# analog_filterung.net
KiCad netlist of a schematic drawn in Altium Designer
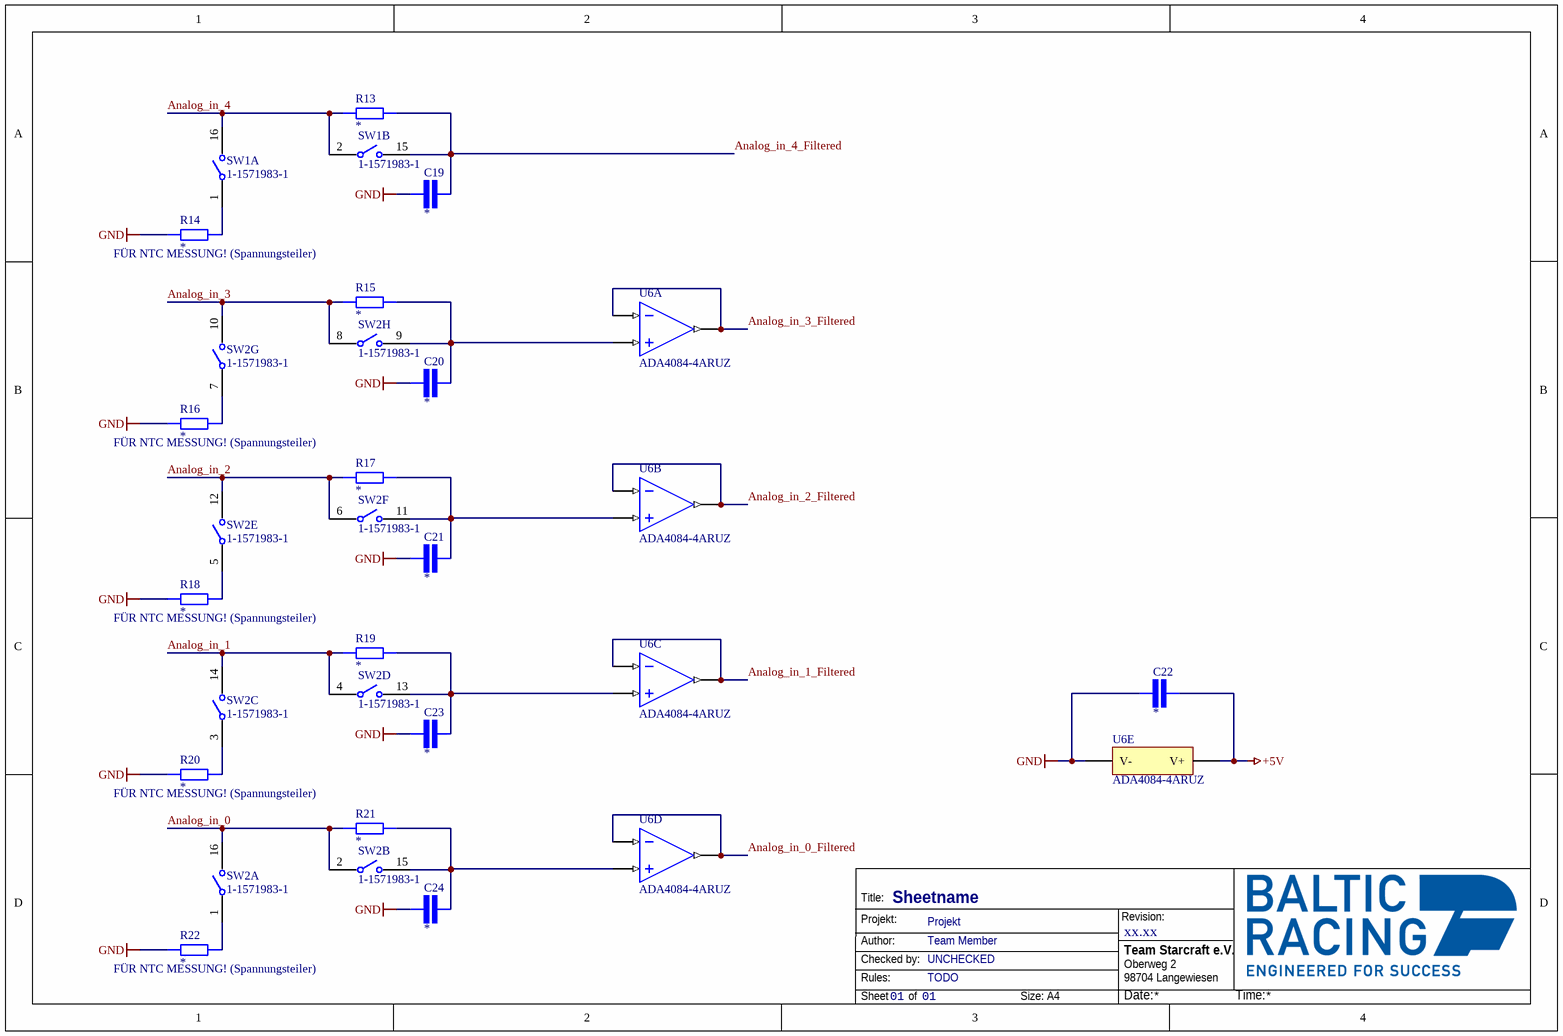
[diagram p0: analog filterung.SchDoc]

(export (version "E")
  (design (tool "Eeschema 10.0.6"))
  (components
    (comp (ref "C19")
      (value "SMD Capacitor")
      (footprint "CAP 0603/1608")
      (description "Capacitor with multiple Footprints")
      (fields (field (name "ALTIUM_VALUE") "*"))
      (libsource (lib "") (part "SMD Capacitor_1"))
    )
    (comp (ref "C20")
      (value "SMD Capacitor")
      (footprint "CAP 0603/1608")
      (description "Capacitor with multiple Footprints")
      (fields (field (name "ALTIUM_VALUE") "*"))
      (libsource (lib "") (part "SMD Capacitor_1"))
    )
    (comp (ref "C21")
      (value "SMD Capacitor")
      (footprint "CAP 0603/1608")
      (description "Capacitor with multiple Footprints")
      (fields (field (name "ALTIUM_VALUE") "*"))
      (libsource (lib "") (part "SMD Capacitor_1"))
    )
    (comp (ref "C22")
      (value "SMD Capacitor")
      (footprint "CAP 0603/1608")
      (description "Capacitor with multiple Footprints")
      (fields (field (name "ALTIUM_VALUE") "*"))
      (libsource (lib "Standardbauteile") (part "SMD Capacitor"))
    )
    (comp (ref "C23")
      (value "SMD Capacitor")
      (footprint "CAP 0603/1608")
      (description "Capacitor with multiple Footprints")
      (fields (field (name "ALTIUM_VALUE") "*"))
      (libsource (lib "") (part "SMD Capacitor_1"))
    )
    (comp (ref "C24")
      (value "SMD Capacitor")
      (footprint "CAP 0603/1608")
      (description "Capacitor with multiple Footprints")
      (fields (field (name "ALTIUM_VALUE") "*"))
      (libsource (lib "") (part "SMD Capacitor_1"))
    )
    (comp (ref "R13")
      (value "SMD Resistor")
      (footprint "STACKPOLE CSR0603")
      (description "Resistor with multiple footprints")
      (fields (field (name "ALTIUM_VALUE") "*"))
      (libsource (lib "Standardbauteile") (part "SMD Resistor"))
    )
    (comp (ref "R14")
      (value "SMD Resistor")
      (footprint "STACKPOLE CSR0603")
      (description "Resistor with multiple footprints")
      (fields (field (name "ALTIUM_VALUE") "*"))
      (libsource (lib "Standardbauteile") (part "SMD Resistor"))
    )
    (comp (ref "R15")
      (value "SMD Resistor")
      (footprint "STACKPOLE CSR0603")
      (description "Resistor with multiple footprints")
      (fields (field (name "ALTIUM_VALUE") "*"))
      (libsource (lib "Standardbauteile") (part "SMD Resistor"))
    )
    (comp (ref "R16")
      (value "SMD Resistor")
      (footprint "STACKPOLE CSR0603")
      (description "Resistor with multiple footprints")
      (fields (field (name "ALTIUM_VALUE") "*"))
      (libsource (lib "Standardbauteile") (part "SMD Resistor"))
    )
    (comp (ref "R17")
      (value "SMD Resistor")
      (footprint "STACKPOLE CSR0603")
      (description "Resistor with multiple footprints")
      (fields (field (name "ALTIUM_VALUE") "*"))
      (libsource (lib "Standardbauteile") (part "SMD Resistor"))
    )
    (comp (ref "R18")
      (value "SMD Resistor")
      (footprint "STACKPOLE CSR0603")
      (description "Resistor with multiple footprints")
      (fields (field (name "ALTIUM_VALUE") "*"))
      (libsource (lib "Standardbauteile") (part "SMD Resistor"))
    )
    (comp (ref "R19")
      (value "SMD Resistor")
      (footprint "STACKPOLE CSR0603")
      (description "Resistor with multiple footprints")
      (fields (field (name "ALTIUM_VALUE") "*"))
      (libsource (lib "Standardbauteile") (part "SMD Resistor"))
    )
    (comp (ref "R20")
      (value "SMD Resistor")
      (footprint "STACKPOLE CSR0603")
      (description "Resistor with multiple footprints")
      (fields (field (name "ALTIUM_VALUE") "*"))
      (libsource (lib "Standardbauteile") (part "SMD Resistor"))
    )
    (comp (ref "R21")
      (value "SMD Resistor")
      (footprint "STACKPOLE CSR0603")
      (description "Resistor with multiple footprints")
      (fields (field (name "ALTIUM_VALUE") "*"))
      (libsource (lib "Standardbauteile") (part "SMD Resistor"))
    )
    (comp (ref "R22")
      (value "SMD Resistor")
      (footprint "STACKPOLE CSR0603")
      (description "Resistor with multiple footprints")
      (fields (field (name "ALTIUM_VALUE") "*"))
      (libsource (lib "Standardbauteile") (part "SMD Resistor"))
    )
    (comp (ref "SW1")
      (value "1-1571983-1")
      (footprint "FP-1-1571983-1-MFG")
      (description "SWITCH SLIDE DIP SPST 25MA 24V")
      (fields
        (field (name "MANUFACTURER") "TE Connectivity")
        (field (name "OCTOPART") "https://octopart.com/1-1571983-1-te+connectivity-40115518")
      )
      (libsource (lib "Altium Content Vault") (part "970e54b12a704161c1b4a03f85903bf"))
    )
    (comp (ref "SW2")
      (value "1-1571983-1")
      (footprint "FP-1-1571983-1-MFG")
      (description "SWITCH SLIDE DIP SPST 25MA 24V")
      (fields
        (field (name "MANUFACTURER") "TE Connectivity")
        (field (name "OCTOPART") "https://octopart.com/1-1571983-1-te+connectivity-40115518")
      )
      (libsource (lib "Altium Content Vault") (part "970e54b12a704161c1b4a03f85903bf"))
    )
    (comp (ref "U6")
      (value "ADA4084-4ARUZ")
      (footprint "ANALOG_RU14")
      (description "30 V, Low Noise, Rail-to-Rail Input/Output, Low Power Operational Amplifiers")
      (libsource (lib "") (part "ADA4084-4ARUZ_1"))
    )
  )
  (nets
    (net (code "1") (name "+5V") (class "Default")
      (node (ref "C22") (pin "1") (pinfunction "1_1") (pintype "passive"))
      (node (ref "U6") (pin "4") (pinfunction "V+_4") (pintype "power_in"))
    )
    (net (code "2") (name "/Analog_in_0") (class "Default")
      (node (ref "R21") (pin "2") (pinfunction "2_2") (pintype "passive"))
      (node (ref "SW2") (pin "16") (pinfunction "16_16") (pintype "passive"))
      (node (ref "SW2") (pin "2") (pinfunction "2_2") (pintype "passive"))
    )
    (net (code "3") (name "/Analog_in_0_Filtered") (class "Default")
      (node (ref "U6") (pin "13") (pinfunction "-IN_D_13") (pintype "input"))
      (node (ref "U6") (pin "14") (pinfunction "OUT_D_14") (pintype "output"))
    )
    (net (code "4") (name "/Analog_in_1") (class "Default")
      (node (ref "R19") (pin "2") (pinfunction "2_2") (pintype "passive"))
      (node (ref "SW2") (pin "14") (pinfunction "14_14") (pintype "passive"))
      (node (ref "SW2") (pin "4") (pinfunction "4_4") (pintype "passive"))
    )
    (net (code "5") (name "/Analog_in_1_Filtered") (class "Default")
      (node (ref "U6") (pin "8") (pinfunction "OUT_C_8") (pintype "output"))
      (node (ref "U6") (pin "9") (pinfunction "-IN_C_9") (pintype "input"))
    )
    (net (code "6") (name "/Analog_in_2") (class "Default")
      (node (ref "R17") (pin "2") (pinfunction "2_2") (pintype "passive"))
      (node (ref "SW2") (pin "12") (pinfunction "12_12") (pintype "passive"))
      (node (ref "SW2") (pin "6") (pinfunction "6_6") (pintype "passive"))
    )
    (net (code "7") (name "/Analog_in_2_Filtered") (class "Default")
      (node (ref "U6") (pin "6") (pinfunction "-IN_B_6") (pintype "input"))
      (node (ref "U6") (pin "7") (pinfunction "OUT_B_7") (pintype "output"))
    )
    (net (code "8") (name "/Analog_in_3") (class "Default")
      (node (ref "R15") (pin "2") (pinfunction "2_2") (pintype "passive"))
      (node (ref "SW2") (pin "10") (pinfunction "10_10") (pintype "passive"))
      (node (ref "SW2") (pin "8") (pinfunction "8_8") (pintype "passive"))
    )
    (net (code "9") (name "/Analog_in_3_Filtered") (class "Default")
      (node (ref "U6") (pin "1") (pinfunction "OUT_A_1") (pintype "output"))
      (node (ref "U6") (pin "2") (pinfunction "-IN_A_2") (pintype "input"))
    )
    (net (code "10") (name "/Analog_in_4") (class "Default")
      (node (ref "R13") (pin "2") (pinfunction "2_2") (pintype "passive"))
      (node (ref "SW1") (pin "16") (pinfunction "16_16") (pintype "passive"))
      (node (ref "SW1") (pin "2") (pinfunction "2_2") (pintype "passive"))
    )
    (net (code "11") (name "/Analog_in_4_Filtered") (class "Default")
      (node (ref "C19") (pin "2") (pinfunction "2_2") (pintype "passive"))
      (node (ref "R13") (pin "1") (pinfunction "1_1") (pintype "passive"))
      (node (ref "SW1") (pin "15") (pinfunction "15_15") (pintype "passive"))
    )
    (net (code "12") (name "GND") (class "Default")
      (node (ref "C19") (pin "1") (pinfunction "1_1") (pintype "passive"))
      (node (ref "C20") (pin "1") (pinfunction "1_1") (pintype "passive"))
      (node (ref "C21") (pin "1") (pinfunction "1_1") (pintype "passive"))
      (node (ref "C22") (pin "2") (pinfunction "2_2") (pintype "passive"))
      (node (ref "C23") (pin "1") (pinfunction "1_1") (pintype "passive"))
      (node (ref "C24") (pin "1") (pinfunction "1_1") (pintype "passive"))
      (node (ref "R14") (pin "1") (pinfunction "1_1") (pintype "passive"))
      (node (ref "R16") (pin "1") (pinfunction "1_1") (pintype "passive"))
      (node (ref "R18") (pin "1") (pinfunction "1_1") (pintype "passive"))
      (node (ref "R20") (pin "1") (pinfunction "1_1") (pintype "passive"))
      (node (ref "R22") (pin "1") (pinfunction "1_1") (pintype "passive"))
      (node (ref "U6") (pin "11") (pinfunction "V-_11") (pintype "power_in"))
    )
    (net (code "13") (name "Net-(R14-Pad2)") (class "Default")
      (node (ref "R14") (pin "2") (pinfunction "2_2") (pintype "passive"))
      (node (ref "SW1") (pin "1") (pinfunction "1_1") (pintype "passive"))
    )
    (net (code "14") (name "Net-(R16-Pad2)") (class "Default")
      (node (ref "R16") (pin "2") (pinfunction "2_2") (pintype "passive"))
      (node (ref "SW2") (pin "7") (pinfunction "7_7") (pintype "passive"))
    )
    (net (code "15") (name "Net-(R18-Pad2)") (class "Default")
      (node (ref "R18") (pin "2") (pinfunction "2_2") (pintype "passive"))
      (node (ref "SW2") (pin "5") (pinfunction "5_5") (pintype "passive"))
    )
    (net (code "16") (name "Net-(R20-Pad2)") (class "Default")
      (node (ref "R20") (pin "2") (pinfunction "2_2") (pintype "passive"))
      (node (ref "SW2") (pin "3") (pinfunction "3_3") (pintype "passive"))
    )
    (net (code "17") (name "Net-(R22-Pad2)") (class "Default")
      (node (ref "R22") (pin "2") (pinfunction "2_2") (pintype "passive"))
      (node (ref "SW2") (pin "1") (pinfunction "1_1") (pintype "passive"))
    )
    (net (code "18") (name "Net-(U6A-+IN_A)") (class "Default")
      (node (ref "C20") (pin "2") (pinfunction "2_2") (pintype "passive"))
      (node (ref "R15") (pin "1") (pinfunction "1_1") (pintype "passive"))
      (node (ref "SW2") (pin "9") (pinfunction "9_9") (pintype "passive"))
      (node (ref "U6") (pin "3") (pinfunction "+IN_A_3") (pintype "input"))
    )
    (net (code "19") (name "Net-(U6B-+IN_B)") (class "Default")
      (node (ref "C21") (pin "2") (pinfunction "2_2") (pintype "passive"))
      (node (ref "R17") (pin "1") (pinfunction "1_1") (pintype "passive"))
      (node (ref "SW2") (pin "11") (pinfunction "11_11") (pintype "passive"))
      (node (ref "U6") (pin "5") (pinfunction "+IN_B_5") (pintype "input"))
    )
    (net (code "20") (name "Net-(U6C-+IN_C)") (class "Default")
      (node (ref "C23") (pin "2") (pinfunction "2_2") (pintype "passive"))
      (node (ref "R19") (pin "1") (pinfunction "1_1") (pintype "passive"))
      (node (ref "SW2") (pin "13") (pinfunction "13_13") (pintype "passive"))
      (node (ref "U6") (pin "10") (pinfunction "+IN_C_10") (pintype "input"))
    )
    (net (code "21") (name "Net-(U6D-+IN_D)") (class "Default")
      (node (ref "C24") (pin "2") (pinfunction "2_2") (pintype "passive"))
      (node (ref "R21") (pin "1") (pinfunction "1_1") (pintype "passive"))
      (node (ref "SW2") (pin "15") (pinfunction "15_15") (pintype "passive"))
      (node (ref "U6") (pin "12") (pinfunction "+IN_D_12") (pintype "input"))
    )
  )
)
